# ATMEGA8535.net
KiCad netlist of a schematic drawn in EAGLE
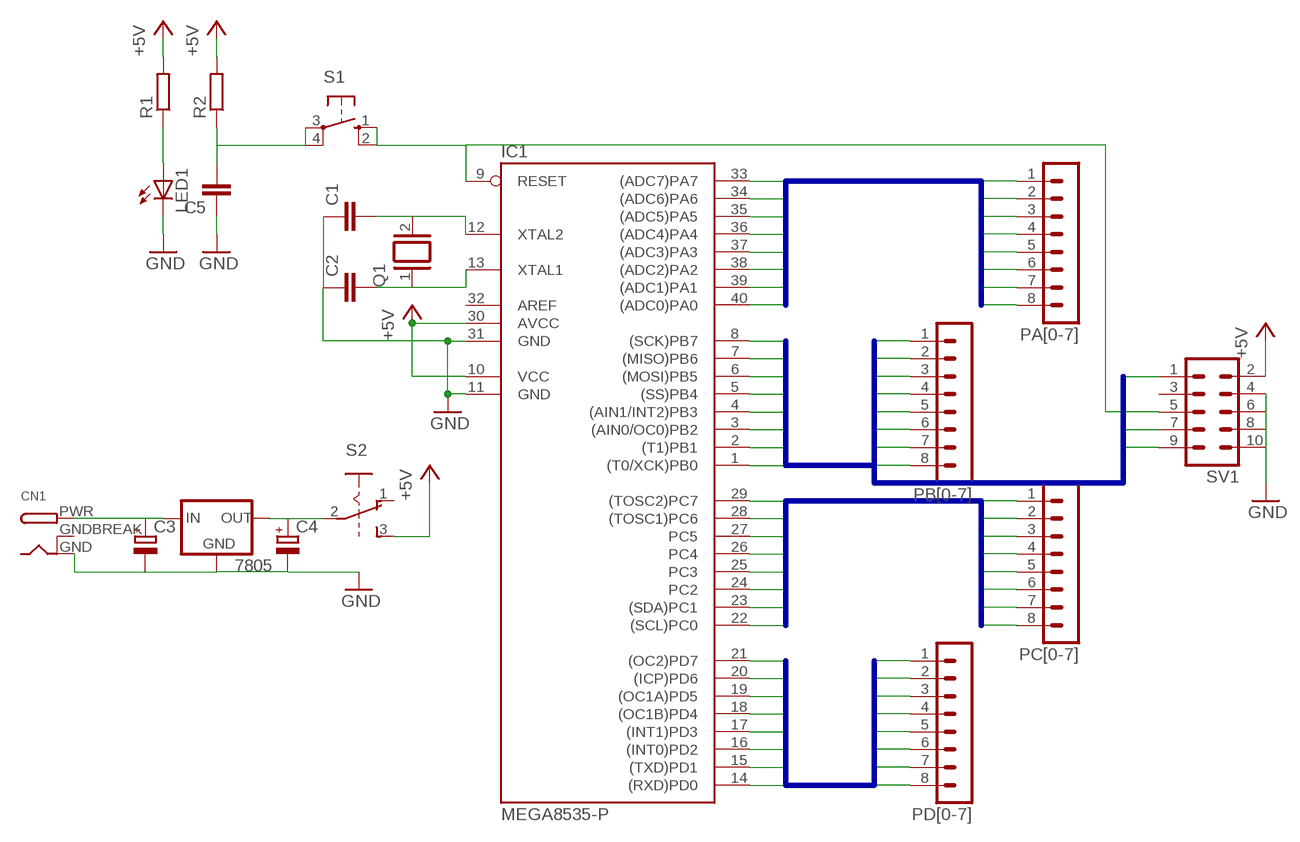
[diagram p0: schematic, sheet 1]

(export (version "E")
  (design (tool "Eeschema 10.0.6"))
  (components
    (comp (ref "7805")
      (value "78XXL")
      (footprint "eagle-import:78XXL")
      (libsource (lib "eagle-import") (part "78XXL"))
    )
    (comp (ref "C1")
      (value "C-EU025-025X050")
      (footprint "eagle-import:C025-025X050")
      (libsource (lib "eagle-import") (part "C-EU025-025X050"))
    )
    (comp (ref "C2")
      (value "C-EU025-025X050")
      (footprint "eagle-import:C025-025X050")
      (libsource (lib "eagle-import") (part "C-EU025-025X050"))
    )
    (comp (ref "C3")
      (value "CPOL-EUE2.5-5")
      (footprint "eagle-import:E2,5-5")
      (libsource (lib "eagle-import") (part "CPOL-EUE2.5-5"))
    )
    (comp (ref "C4")
      (value "CPOL-EUE2.5-5")
      (footprint "eagle-import:E2,5-5")
      (libsource (lib "eagle-import") (part "CPOL-EUE2.5-5"))
    )
    (comp (ref "C5")
      (value "C-EU050-025X075")
      (footprint "eagle-import:C050-025X075")
      (libsource (lib "eagle-import") (part "C-EU050-025X075"))
    )
    (comp (ref "CN1")
      (value "DCBARRELPTH")
      (footprint "eagle-import:DCJACK_2MM_PTH")
      (libsource (lib "eagle-import") (part "DCBARRELPTH"))
    )
    (comp (ref "IC1")
      (value "MEGA8535-P")
      (footprint "eagle-import:DIL40")
      (fields (field (name "MPN") "ATMEGA8535-16PU"))
      (libsource (lib "eagle-import") (part "MEGA8535-P"))
    )
    (comp (ref "LED1")
      (value "LED5MM")
      (footprint "eagle-import:LED5MM")
      (libsource (lib "eagle-import") (part "LED5MM"))
    )
    (comp (ref "PA[0-7]")
      (value "MA08-1")
      (footprint "eagle-import:MA08-1")
      (libsource (lib "eagle-import") (part "MA08-1"))
    )
    (comp (ref "PB[0-7]")
      (value "MA08-1")
      (footprint "eagle-import:MA08-1")
      (libsource (lib "eagle-import") (part "MA08-1"))
    )
    (comp (ref "PC[0-7]")
      (value "MA08-1")
      (footprint "eagle-import:MA08-1")
      (libsource (lib "eagle-import") (part "MA08-1"))
    )
    (comp (ref "PD[0-7]")
      (value "MA08-1")
      (footprint "eagle-import:MA08-1")
      (libsource (lib "eagle-import") (part "MA08-1"))
    )
    (comp (ref "Q1")
      (value "XTAL/S")
      (footprint "eagle-import:QS")
      (libsource (lib "eagle-import") (part "XTAL/S"))
    )
    (comp (ref "R1")
      (value "R-EU_0207/7")
      (footprint "eagle-import:0207_7")
      (libsource (lib "eagle-import") (part "R-EU_0207/7"))
    )
    (comp (ref "R2")
      (value "R-EU_0207/7")
      (footprint "eagle-import:0207_7")
      (libsource (lib "eagle-import") (part "R-EU_0207/7"))
    )
    (comp (ref "S1")
      (value "10-XX")
      (footprint "eagle-import:B3F-10XX")
      (fields (field (name "MPN") "B3F-1000"))
      (libsource (lib "eagle-import") (part "10-XX"))
    )
    (comp (ref "S2")
      (value "A68-A31")
      (footprint "eagle-import:A68-A31")
      (libsource (lib "eagle-import") (part "A68-A31"))
    )
    (comp (ref "SV1")
      (value "MA05-2")
      (footprint "eagle-import:MA05-2")
      (libsource (lib "eagle-import") (part "MA05-2"))
    )
  )
  (nets
    (net (code "1") (name "+5V") (class "Default")
      (node (ref "IC1") (pin "10") (pinfunction "VCC_10") (pintype "power_in"))
      (node (ref "IC1") (pin "30") (pinfunction "AVCC_30") (pintype "power_in"))
      (node (ref "R1") (pin "2") (pinfunction "2_2") (pintype "passive"))
      (node (ref "R2") (pin "2") (pinfunction "2_2") (pintype "passive"))
      (node (ref "S2") (pin "3") (pinfunction "S_3") (pintype "passive"))
      (node (ref "SV1") (pin "2") (pinfunction "2_2") (pintype "passive"))
    )
    (net (code "2") (name "/GNDBREAK") (class "Default")
      (node (ref "CN1") (pin "GNDBREAK") (pinfunction "GNDBREAK_GNDBREAK") (pintype "power_in"))
    )
    (net (code "3") (name "/PA0") (class "Default")
      (node (ref "IC1") (pin "40") (pinfunction "(ADC0)PA0_40") (pintype "bidirectional"))
      (node (ref "PA[0-7]") (pin "1") (pinfunction "1_1") (pintype "passive"))
    )
    (net (code "4") (name "/PA1") (class "Default")
      (node (ref "IC1") (pin "39") (pinfunction "(ADC1)PA1_39") (pintype "bidirectional"))
      (node (ref "PA[0-7]") (pin "2") (pinfunction "2_2") (pintype "passive"))
    )
    (net (code "5") (name "/PA2") (class "Default")
      (node (ref "IC1") (pin "38") (pinfunction "(ADC2)PA2_38") (pintype "bidirectional"))
      (node (ref "PA[0-7]") (pin "3") (pinfunction "3_3") (pintype "passive"))
    )
    (net (code "6") (name "/PA3") (class "Default")
      (node (ref "IC1") (pin "37") (pinfunction "(ADC3)PA3_37") (pintype "bidirectional"))
      (node (ref "PA[0-7]") (pin "4") (pinfunction "4_4") (pintype "passive"))
    )
    (net (code "7") (name "/PA4") (class "Default")
      (node (ref "IC1") (pin "36") (pinfunction "(ADC4)PA4_36") (pintype "bidirectional"))
      (node (ref "PA[0-7]") (pin "5") (pinfunction "5_5") (pintype "passive"))
    )
    (net (code "8") (name "/PA5") (class "Default")
      (node (ref "IC1") (pin "35") (pinfunction "(ADC5)PA5_35") (pintype "bidirectional"))
      (node (ref "PA[0-7]") (pin "6") (pinfunction "6_6") (pintype "passive"))
    )
    (net (code "9") (name "/PA6") (class "Default")
      (node (ref "IC1") (pin "34") (pinfunction "(ADC6)PA6_34") (pintype "bidirectional"))
      (node (ref "PA[0-7]") (pin "7") (pinfunction "7_7") (pintype "passive"))
    )
    (net (code "10") (name "/PA7") (class "Default")
      (node (ref "IC1") (pin "33") (pinfunction "(ADC7)PA7_33") (pintype "bidirectional"))
      (node (ref "PA[0-7]") (pin "8") (pinfunction "8_8") (pintype "passive"))
    )
    (net (code "11") (name "/PB0") (class "Default")
      (node (ref "IC1") (pin "1") (pinfunction "(T0/XCK)PB0_1") (pintype "bidirectional"))
      (node (ref "PB[0-7]") (pin "1") (pinfunction "1_1") (pintype "passive"))
    )
    (net (code "12") (name "/PB1") (class "Default")
      (node (ref "IC1") (pin "2") (pinfunction "(T1)PB1_2") (pintype "bidirectional"))
      (node (ref "PB[0-7]") (pin "2") (pinfunction "2_2") (pintype "passive"))
    )
    (net (code "13") (name "/PB2") (class "Default")
      (node (ref "IC1") (pin "3") (pinfunction "(AIN0/OC0)PB2_3") (pintype "bidirectional"))
      (node (ref "PB[0-7]") (pin "3") (pinfunction "3_3") (pintype "passive"))
    )
    (net (code "14") (name "/PB3") (class "Default")
      (node (ref "IC1") (pin "4") (pinfunction "(AIN1/INT2)PB3_4") (pintype "bidirectional"))
      (node (ref "PB[0-7]") (pin "4") (pinfunction "4_4") (pintype "passive"))
    )
    (net (code "15") (name "/PB4") (class "Default")
      (node (ref "IC1") (pin "5") (pinfunction "(SS)PB4_5") (pintype "bidirectional"))
      (node (ref "PB[0-7]") (pin "5") (pinfunction "5_5") (pintype "passive"))
    )
    (net (code "16") (name "/PB5") (class "Default")
      (node (ref "IC1") (pin "6") (pinfunction "(MOSI)PB5_6") (pintype "bidirectional"))
      (node (ref "PB[0-7]") (pin "6") (pinfunction "6_6") (pintype "passive"))
      (node (ref "SV1") (pin "1") (pinfunction "1_1") (pintype "passive"))
    )
    (net (code "17") (name "/PB6") (class "Default")
      (node (ref "IC1") (pin "7") (pinfunction "(MISO)PB6_7") (pintype "bidirectional"))
      (node (ref "PB[0-7]") (pin "7") (pinfunction "7_7") (pintype "passive"))
      (node (ref "SV1") (pin "9") (pinfunction "9_9") (pintype "passive"))
    )
    (net (code "18") (name "/PB7") (class "Default")
      (node (ref "IC1") (pin "8") (pinfunction "(SCK)PB7_8") (pintype "bidirectional"))
      (node (ref "PB[0-7]") (pin "8") (pinfunction "8_8") (pintype "passive"))
      (node (ref "SV1") (pin "7") (pinfunction "7_7") (pintype "passive"))
    )
    (net (code "19") (name "/PC0") (class "Default")
      (node (ref "IC1") (pin "22") (pinfunction "(SCL)PC0_22") (pintype "bidirectional"))
      (node (ref "PC[0-7]") (pin "1") (pinfunction "1_1") (pintype "passive"))
    )
    (net (code "20") (name "/PC1") (class "Default")
      (node (ref "IC1") (pin "23") (pinfunction "(SDA)PC1_23") (pintype "bidirectional"))
      (node (ref "PC[0-7]") (pin "2") (pinfunction "2_2") (pintype "passive"))
    )
    (net (code "21") (name "/PC2") (class "Default")
      (node (ref "IC1") (pin "24") (pinfunction "PC2_24") (pintype "bidirectional"))
      (node (ref "PC[0-7]") (pin "3") (pinfunction "3_3") (pintype "passive"))
    )
    (net (code "22") (name "/PC3") (class "Default")
      (node (ref "IC1") (pin "25") (pinfunction "PC3_25") (pintype "bidirectional"))
      (node (ref "PC[0-7]") (pin "4") (pinfunction "4_4") (pintype "passive"))
    )
    (net (code "23") (name "/PC4") (class "Default")
      (node (ref "IC1") (pin "26") (pinfunction "PC4_26") (pintype "bidirectional"))
      (node (ref "PC[0-7]") (pin "5") (pinfunction "5_5") (pintype "passive"))
    )
    (net (code "24") (name "/PC5") (class "Default")
      (node (ref "IC1") (pin "27") (pinfunction "PC5_27") (pintype "bidirectional"))
      (node (ref "PC[0-7]") (pin "6") (pinfunction "6_6") (pintype "passive"))
    )
    (net (code "25") (name "/PC6") (class "Default")
      (node (ref "IC1") (pin "28") (pinfunction "(TOSC1)PC6_28") (pintype "bidirectional"))
      (node (ref "PC[0-7]") (pin "7") (pinfunction "7_7") (pintype "passive"))
    )
    (net (code "26") (name "/PC7") (class "Default")
      (node (ref "IC1") (pin "29") (pinfunction "(TOSC2)PC7_29") (pintype "bidirectional"))
      (node (ref "PC[0-7]") (pin "8") (pinfunction "8_8") (pintype "passive"))
    )
    (net (code "27") (name "/PD0") (class "Default")
      (node (ref "IC1") (pin "14") (pinfunction "(RXD)PD0_14") (pintype "bidirectional"))
      (node (ref "PD[0-7]") (pin "1") (pinfunction "1_1") (pintype "passive"))
    )
    (net (code "28") (name "/PD1") (class "Default")
      (node (ref "IC1") (pin "15") (pinfunction "(TXD)PD1_15") (pintype "bidirectional"))
      (node (ref "PD[0-7]") (pin "2") (pinfunction "2_2") (pintype "passive"))
    )
    (net (code "29") (name "/PD2") (class "Default")
      (node (ref "IC1") (pin "16") (pinfunction "(INT0)PD2_16") (pintype "bidirectional"))
      (node (ref "PD[0-7]") (pin "3") (pinfunction "3_3") (pintype "passive"))
    )
    (net (code "30") (name "/PD3") (class "Default")
      (node (ref "IC1") (pin "17") (pinfunction "(INT1)PD3_17") (pintype "bidirectional"))
      (node (ref "PD[0-7]") (pin "4") (pinfunction "4_4") (pintype "passive"))
    )
    (net (code "31") (name "/PD4") (class "Default")
      (node (ref "IC1") (pin "18") (pinfunction "(OC1B)PD4_18") (pintype "bidirectional"))
      (node (ref "PD[0-7]") (pin "5") (pinfunction "5_5") (pintype "passive"))
    )
    (net (code "32") (name "/PD5") (class "Default")
      (node (ref "IC1") (pin "19") (pinfunction "(OC1A)PD5_19") (pintype "bidirectional"))
      (node (ref "PD[0-7]") (pin "6") (pinfunction "6_6") (pintype "passive"))
    )
    (net (code "33") (name "/PD6") (class "Default")
      (node (ref "IC1") (pin "20") (pinfunction "(ICP)PD6_20") (pintype "bidirectional"))
      (node (ref "PD[0-7]") (pin "7") (pinfunction "7_7") (pintype "passive"))
    )
    (net (code "34") (name "/PD7") (class "Default")
      (node (ref "IC1") (pin "21") (pinfunction "(OC2)PD7_21") (pintype "bidirectional"))
      (node (ref "PD[0-7]") (pin "8") (pinfunction "8_8") (pintype "passive"))
    )
    (net (code "35") (name "GND") (class "Default")
      (node (ref "7805") (pin "GND") (pinfunction "GND_GND") (pintype "input"))
      (node (ref "C1") (pin "1") (pinfunction "1_1") (pintype "passive"))
      (node (ref "C2") (pin "1") (pinfunction "1_1") (pintype "passive"))
      (node (ref "C3") (pin "-") (pinfunction "-_-") (pintype "passive"))
      (node (ref "C4") (pin "-") (pinfunction "-_-") (pintype "passive"))
      (node (ref "C5") (pin "1") (pinfunction "1_1") (pintype "passive"))
      (node (ref "CN1") (pin "GND") (pinfunction "GND_GND") (pintype "power_in"))
      (node (ref "IC1") (pin "11") (pinfunction "GND_11") (pintype "power_in"))
      (node (ref "IC1") (pin "31") (pinfunction "GND_31") (pintype "power_in"))
      (node (ref "LED1") (pin "K") (pinfunction "C_K") (pintype "passive"))
      (node (ref "SV1") (pin "10") (pinfunction "10_10") (pintype "passive"))
      (node (ref "SV1") (pin "4") (pinfunction "4_4") (pintype "passive"))
      (node (ref "SV1") (pin "6") (pinfunction "6_6") (pintype "passive"))
      (node (ref "SV1") (pin "8") (pinfunction "8_8") (pintype "passive"))
    )
    (net (code "36") (name "Net-(7805-PadIN)") (class "Default")
      (node (ref "7805") (pin "IN") (pinfunction "IN_IN") (pintype "input"))
      (node (ref "C3") (pin "+") (pinfunction "+_+") (pintype "passive"))
      (node (ref "CN1") (pin "PWR") (pinfunction "PWR_PWR") (pintype "power_in"))
    )
    (net (code "37") (name "Net-(IC1-RESET)") (class "Default")
      (node (ref "IC1") (pin "9") (pinfunction "RESET_9") (pintype "input"))
      (node (ref "S1") (pin "1") (pinfunction "S_1") (pintype "passive"))
      (node (ref "S1") (pin "2") (pinfunction "S1_2") (pintype "passive"))
      (node (ref "SV1") (pin "5") (pinfunction "5_5") (pintype "passive"))
    )
    (net (code "38") (name "Net-(IC1-XTAL1)") (class "Default")
      (node (ref "C2") (pin "2") (pinfunction "2_2") (pintype "passive"))
      (node (ref "IC1") (pin "13") (pinfunction "XTAL1_13") (pintype "bidirectional"))
      (node (ref "Q1") (pin "1") (pinfunction "1_1") (pintype "passive"))
    )
    (net (code "39") (name "Net-(IC1-XTAL2)") (class "Default")
      (node (ref "C1") (pin "2") (pinfunction "2_2") (pintype "passive"))
      (node (ref "IC1") (pin "12") (pinfunction "XTAL2_12") (pintype "bidirectional"))
      (node (ref "Q1") (pin "2") (pinfunction "2_2") (pintype "passive"))
    )
    (net (code "40") (name "Net-(LED1-PadA)") (class "Default")
      (node (ref "LED1") (pin "A") (pinfunction "A_A") (pintype "passive"))
      (node (ref "R1") (pin "1") (pinfunction "1_1") (pintype "passive"))
    )
    (net (code "41") (name "Net-(S1-P)") (class "Default")
      (node (ref "C5") (pin "2") (pinfunction "2_2") (pintype "passive"))
      (node (ref "R2") (pin "1") (pinfunction "1_1") (pintype "passive"))
      (node (ref "S1") (pin "3") (pinfunction "P_3") (pintype "passive"))
      (node (ref "S1") (pin "4") (pinfunction "P1_4") (pintype "passive"))
    )
    (net (code "42") (name "Net-(S2A-P)") (class "Default")
      (node (ref "7805") (pin "OUT") (pinfunction "OUT_OUT") (pintype "passive"))
      (node (ref "C4") (pin "+") (pinfunction "+_+") (pintype "passive"))
      (node (ref "S2") (pin "2") (pinfunction "P_2") (pintype "passive"))
    )
    (net (code "43") (name "unconnected-(IC1-AREF-Pad32)") (class "Default")
      (node (ref "IC1") (pin "32") (pinfunction "AREF_32") (pintype "passive"))
    )
    (net (code "44") (name "unconnected-(S2A-O-Pad1)") (class "Default")
      (node (ref "S2") (pin "1") (pinfunction "O_1") (pintype "passive"))
    )
    (net (code "45") (name "unconnected-(SV1-Pad3)") (class "Default")
      (node (ref "SV1") (pin "3") (pinfunction "3_3") (pintype "passive"))
    )
  )
)
